# Analog.net
KiCad netlist of a schematic drawn in Altium Designer
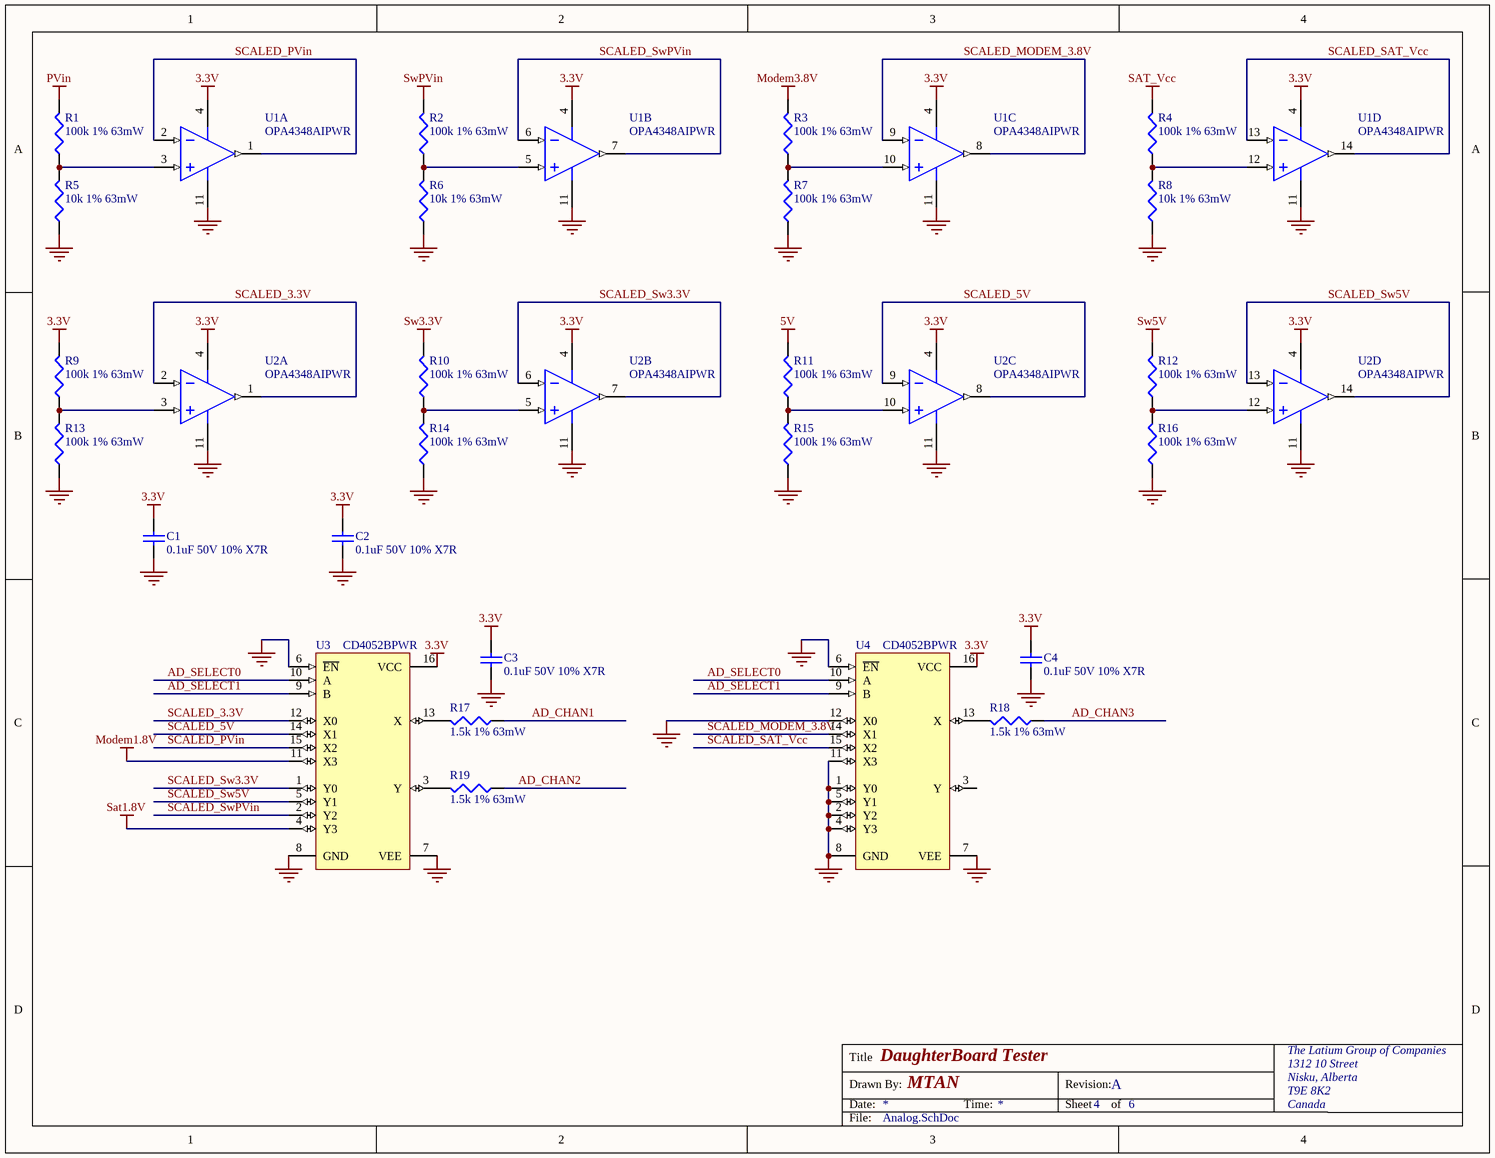
[diagram p0: Analog.SchDoc]

(export (version "E")
  (design (tool "Eeschema 10.0.6"))
  (components
    (comp (ref "C1")
      (value "0.1uF 50V 10% X7R")
      (footprint "CAPC1005L")
      (description "Capacitor")
      (libsource (lib "Miscellaneous Devices") (part "Cap"))
    )
    (comp (ref "C2")
      (value "0.1uF 50V 10% X7R")
      (footprint "CAPC1005L")
      (description "Capacitor")
      (libsource (lib "Miscellaneous Devices") (part "Cap"))
    )
    (comp (ref "C3")
      (value "0.1uF 50V 10% X7R")
      (footprint "CAPC1005L")
      (description "Capacitor")
      (libsource (lib "Miscellaneous Devices") (part "Cap"))
    )
    (comp (ref "C4")
      (value "0.1uF 50V 10% X7R")
      (footprint "CAPC1005L")
      (description "Capacitor")
      (libsource (lib "Miscellaneous Devices") (part "Cap"))
    )
    (comp (ref "R1")
      (value "100k 1% 63mW")
      (footprint "RESC1005L")
      (description "Resistor")
      (libsource (lib "Miscellaneous Devices") (part "Res3"))
    )
    (comp (ref "R2")
      (value "100k 1% 63mW")
      (footprint "RESC1005L")
      (description "Resistor")
      (libsource (lib "Miscellaneous Devices") (part "Res3"))
    )
    (comp (ref "R3")
      (value "100k 1% 63mW")
      (footprint "RESC1005L")
      (description "Resistor")
      (libsource (lib "Miscellaneous Devices") (part "Res3"))
    )
    (comp (ref "R4")
      (value "100k 1% 63mW")
      (footprint "RESC1005L")
      (description "Resistor")
      (libsource (lib "Miscellaneous Devices") (part "Res3"))
    )
    (comp (ref "R5")
      (value "10k 1% 63mW")
      (footprint "RESC1005L")
      (description "Resistor")
      (libsource (lib "Miscellaneous Devices") (part "Res3"))
    )
    (comp (ref "R6")
      (value "10k 1% 63mW")
      (footprint "RESC1005L")
      (description "Resistor")
      (libsource (lib "Miscellaneous Devices") (part "Res3"))
    )
    (comp (ref "R7")
      (value "100k 1% 63mW")
      (footprint "RESC1005L")
      (description "Resistor")
      (libsource (lib "Miscellaneous Devices") (part "Res3"))
    )
    (comp (ref "R8")
      (value "10k 1% 63mW")
      (footprint "RESC1005L")
      (description "Resistor")
      (libsource (lib "Miscellaneous Devices") (part "Res3"))
    )
    (comp (ref "R9")
      (value "100k 1% 63mW")
      (footprint "RESC1005L")
      (description "Resistor")
      (libsource (lib "Miscellaneous Devices") (part "Res3"))
    )
    (comp (ref "R10")
      (value "100k 1% 63mW")
      (footprint "RESC1005L")
      (description "Resistor")
      (libsource (lib "Miscellaneous Devices") (part "Res3"))
    )
    (comp (ref "R11")
      (value "100k 1% 63mW")
      (footprint "RESC1005L")
      (description "Resistor")
      (libsource (lib "Miscellaneous Devices") (part "Res3"))
    )
    (comp (ref "R12")
      (value "100k 1% 63mW")
      (footprint "RESC1005L")
      (description "Resistor")
      (libsource (lib "Miscellaneous Devices") (part "Res3"))
    )
    (comp (ref "R13")
      (value "100k 1% 63mW")
      (footprint "RESC1005L")
      (description "Resistor")
      (libsource (lib "Miscellaneous Devices") (part "Res3"))
    )
    (comp (ref "R14")
      (value "100k 1% 63mW")
      (footprint "RESC1005L")
      (description "Resistor")
      (libsource (lib "Miscellaneous Devices") (part "Res3"))
    )
    (comp (ref "R15")
      (value "100k 1% 63mW")
      (footprint "RESC1005L")
      (description "Resistor")
      (libsource (lib "Miscellaneous Devices") (part "Res3"))
    )
    (comp (ref "R16")
      (value "100k 1% 63mW")
      (footprint "RESC1005L")
      (description "Resistor")
      (libsource (lib "Miscellaneous Devices") (part "Res3"))
    )
    (comp (ref "R17")
      (value "1.5k 1% 63mW")
      (footprint "RESC1005L")
      (description "Resistor")
      (libsource (lib "Miscellaneous Devices") (part "Res3"))
    )
    (comp (ref "R18")
      (value "1.5k 1% 63mW")
      (footprint "RESC1005L")
      (description "Resistor")
      (libsource (lib "Miscellaneous Devices") (part "Res3"))
    )
    (comp (ref "R19")
      (value "1.5k 1% 63mW")
      (footprint "RESC1005L")
      (description "Resistor")
      (libsource (lib "Miscellaneous Devices") (part "Res3"))
    )
    (comp (ref "U1")
      (value "OPA4348AIPWR")
      (footprint "TI-PW14_L")
      (description "IC OPAMP GP 4 CIRCUIT 14TSSOP")
      (fields (field (name "MANUFACTURER") "Texas Instruments"))
      (libsource (lib "TI Amplifiers and Linear Operational Amplifier Precision Amplifier Part One") (part "OPA4348AIPWR"))
    )
    (comp (ref "U2")
      (value "OPA4348AIPWR")
      (footprint "TI-PW14_L")
      (description "IC OPAMP GP 4 CIRCUIT 14TSSOP")
      (fields (field (name "MANUFACTURER") "Texas Instruments"))
      (libsource (lib "TI Amplifiers and Linear Operational Amplifier Precision Amplifier Part One") (part "OPA4348AIPWR"))
    )
    (comp (ref "U3")
      (value "CD4052BPWR")
      (footprint "TSSOP-16_L")
      (description "IC MUX/DEMUX DUAL 4X1 16TSSOP")
      (fields (field (name "MANUFACTURER") "Texas Instruments"))
      (libsource (lib "FSC Logic Multiplexer") (part "CD4052BCM"))
    )
    (comp (ref "U4")
      (value "CD4052BPWR")
      (footprint "TSSOP-16_L")
      (description "IC MUX/DEMUX DUAL 4X1 16TSSOP")
      (fields (field (name "MANUFACTURER") "Texas Instruments"))
      (libsource (lib "FSC Logic Multiplexer") (part "CD4052BCM"))
    )
  )
  (nets
    (net (code "1") (name "/AD_CHAN1") (class "Default")
      (node (ref "R17") (pin "1") (pinfunction "1_1") (pintype "passive"))
    )
    (net (code "2") (name "/AD_CHAN2") (class "Default")
      (node (ref "R19") (pin "1") (pinfunction "1_1") (pintype "passive"))
    )
    (net (code "3") (name "/AD_CHAN3") (class "Default")
      (node (ref "R18") (pin "1") (pinfunction "1_1") (pintype "passive"))
    )
    (net (code "4") (name "/AD_SELECT0") (class "Default")
      (node (ref "U3") (pin "10") (pinfunction "A_10") (pintype "input"))
      (node (ref "U4") (pin "10") (pinfunction "A_10") (pintype "input"))
    )
    (net (code "5") (name "/AD_SELECT1") (class "Default")
      (node (ref "U3") (pin "9") (pinfunction "B_9") (pintype "input"))
      (node (ref "U4") (pin "9") (pinfunction "B_9") (pintype "input"))
    )
    (net (code "6") (name "/SCALED_3.3V") (class "Default")
      (node (ref "U2") (pin "1") (pinfunction "OUT_A_1") (pintype "output"))
      (node (ref "U2") (pin "2") (pinfunction "IN_A-_2") (pintype "input"))
      (node (ref "U3") (pin "12") (pinfunction "X0_12") (pintype "bidirectional"))
    )
    (net (code "7") (name "/SCALED_5V") (class "Default")
      (node (ref "U2") (pin "8") (pinfunction "OUT_C_8") (pintype "output"))
      (node (ref "U2") (pin "9") (pinfunction "IN_C-_9") (pintype "input"))
      (node (ref "U3") (pin "14") (pinfunction "X1_14") (pintype "bidirectional"))
    )
    (net (code "8") (name "/SCALED_MODEM_3.8V") (class "Default")
      (node (ref "U1") (pin "8") (pinfunction "OUT_C_8") (pintype "output"))
      (node (ref "U1") (pin "9") (pinfunction "IN_C-_9") (pintype "input"))
      (node (ref "U4") (pin "14") (pinfunction "X1_14") (pintype "bidirectional"))
    )
    (net (code "9") (name "/SCALED_PVin") (class "Default")
      (node (ref "U1") (pin "1") (pinfunction "OUT_A_1") (pintype "output"))
      (node (ref "U1") (pin "2") (pinfunction "IN_A-_2") (pintype "input"))
      (node (ref "U3") (pin "15") (pinfunction "X2_15") (pintype "bidirectional"))
    )
    (net (code "10") (name "/SCALED_SAT_Vcc") (class "Default")
      (node (ref "U1") (pin "13") (pinfunction "IN_D-_13") (pintype "input"))
      (node (ref "U1") (pin "14") (pinfunction "OUT_D_14") (pintype "output"))
      (node (ref "U4") (pin "15") (pinfunction "X2_15") (pintype "bidirectional"))
    )
    (net (code "11") (name "/SCALED_Sw3.3V") (class "Default")
      (node (ref "U2") (pin "6") (pinfunction "IN_B-_6") (pintype "input"))
      (node (ref "U2") (pin "7") (pinfunction "OUT_B_7") (pintype "output"))
      (node (ref "U3") (pin "1") (pinfunction "Y0_1") (pintype "bidirectional"))
    )
    (net (code "12") (name "/SCALED_Sw5V") (class "Default")
      (node (ref "U2") (pin "13") (pinfunction "IN_D-_13") (pintype "input"))
      (node (ref "U2") (pin "14") (pinfunction "OUT_D_14") (pintype "output"))
      (node (ref "U3") (pin "5") (pinfunction "Y1_5") (pintype "bidirectional"))
    )
    (net (code "13") (name "/SCALED_SwPVin") (class "Default")
      (node (ref "U1") (pin "6") (pinfunction "IN_B-_6") (pintype "input"))
      (node (ref "U1") (pin "7") (pinfunction "OUT_B_7") (pintype "output"))
      (node (ref "U3") (pin "2") (pinfunction "Y2_2") (pintype "bidirectional"))
    )
    (net (code "14") (name "3.3V") (class "Default")
      (node (ref "C1") (pin "1") (pinfunction "1_1") (pintype "passive"))
      (node (ref "C2") (pin "1") (pinfunction "1_1") (pintype "passive"))
      (node (ref "C3") (pin "1") (pinfunction "1_1") (pintype "passive"))
      (node (ref "C4") (pin "1") (pinfunction "1_1") (pintype "passive"))
      (node (ref "R9") (pin "2") (pinfunction "2_2") (pintype "passive"))
      (node (ref "U1") (pin "4") (pinfunction "V+_4") (pintype "power_in"))
      (node (ref "U2") (pin "4") (pinfunction "V+_4") (pintype "power_in"))
      (node (ref "U3") (pin "16") (pinfunction "VCC_16") (pintype "power_in"))
      (node (ref "U4") (pin "16") (pinfunction "VCC_16") (pintype "power_in"))
    )
    (net (code "15") (name "5V") (class "Default")
      (node (ref "R11") (pin "2") (pinfunction "2_2") (pintype "passive"))
    )
    (net (code "16") (name "GND") (class "Default")
      (node (ref "C1") (pin "2") (pinfunction "2_2") (pintype "passive"))
      (node (ref "C2") (pin "2") (pinfunction "2_2") (pintype "passive"))
      (node (ref "C3") (pin "2") (pinfunction "2_2") (pintype "passive"))
      (node (ref "C4") (pin "2") (pinfunction "2_2") (pintype "passive"))
      (node (ref "R13") (pin "1") (pinfunction "1_1") (pintype "passive"))
      (node (ref "R14") (pin "1") (pinfunction "1_1") (pintype "passive"))
      (node (ref "R15") (pin "1") (pinfunction "1_1") (pintype "passive"))
      (node (ref "R16") (pin "1") (pinfunction "1_1") (pintype "passive"))
      (node (ref "R5") (pin "1") (pinfunction "1_1") (pintype "passive"))
      (node (ref "R6") (pin "1") (pinfunction "1_1") (pintype "passive"))
      (node (ref "R7") (pin "1") (pinfunction "1_1") (pintype "passive"))
      (node (ref "R8") (pin "1") (pinfunction "1_1") (pintype "passive"))
      (node (ref "U1") (pin "11") (pinfunction "V-_11") (pintype "power_in"))
      (node (ref "U2") (pin "11") (pinfunction "V-_11") (pintype "power_in"))
      (node (ref "U3") (pin "6") (pinfunction "~{EN}_6") (pintype "input"))
      (node (ref "U3") (pin "7") (pinfunction "VEE_7") (pintype "power_in"))
      (node (ref "U3") (pin "8") (pinfunction "GND_8") (pintype "power_in"))
      (node (ref "U4") (pin "1") (pinfunction "Y0_1") (pintype "bidirectional"))
      (node (ref "U4") (pin "11") (pinfunction "X3_11") (pintype "bidirectional"))
      (node (ref "U4") (pin "12") (pinfunction "X0_12") (pintype "bidirectional"))
      (node (ref "U4") (pin "2") (pinfunction "Y2_2") (pintype "bidirectional"))
      (node (ref "U4") (pin "4") (pinfunction "Y3_4") (pintype "bidirectional"))
      (node (ref "U4") (pin "5") (pinfunction "Y1_5") (pintype "bidirectional"))
      (node (ref "U4") (pin "6") (pinfunction "~{EN}_6") (pintype "input"))
      (node (ref "U4") (pin "7") (pinfunction "VEE_7") (pintype "power_in"))
      (node (ref "U4") (pin "8") (pinfunction "GND_8") (pintype "power_in"))
    )
    (net (code "17") (name "Modem1.8V") (class "Default")
      (node (ref "U3") (pin "11") (pinfunction "X3_11") (pintype "bidirectional"))
    )
    (net (code "18") (name "Modem3.8V") (class "Default")
      (node (ref "R3") (pin "2") (pinfunction "2_2") (pintype "passive"))
    )
    (net (code "19") (name "Net-(U1A-IN_A+)") (class "Default")
      (node (ref "R1") (pin "1") (pinfunction "1_1") (pintype "passive"))
      (node (ref "R5") (pin "2") (pinfunction "2_2") (pintype "passive"))
      (node (ref "U1") (pin "3") (pinfunction "IN_A+_3") (pintype "input"))
    )
    (net (code "20") (name "Net-(U1B-IN_B+)") (class "Default")
      (node (ref "R2") (pin "1") (pinfunction "1_1") (pintype "passive"))
      (node (ref "R6") (pin "2") (pinfunction "2_2") (pintype "passive"))
      (node (ref "U1") (pin "5") (pinfunction "IN_B+_5") (pintype "input"))
    )
    (net (code "21") (name "Net-(U1C-IN_C+)") (class "Default")
      (node (ref "R3") (pin "1") (pinfunction "1_1") (pintype "passive"))
      (node (ref "R7") (pin "2") (pinfunction "2_2") (pintype "passive"))
      (node (ref "U1") (pin "10") (pinfunction "IN_C+_10") (pintype "input"))
    )
    (net (code "22") (name "Net-(U1D-IN_D+)") (class "Default")
      (node (ref "R4") (pin "1") (pinfunction "1_1") (pintype "passive"))
      (node (ref "R8") (pin "2") (pinfunction "2_2") (pintype "passive"))
      (node (ref "U1") (pin "12") (pinfunction "IN_D+_12") (pintype "input"))
    )
    (net (code "23") (name "Net-(U2A-IN_A+)") (class "Default")
      (node (ref "R13") (pin "2") (pinfunction "2_2") (pintype "passive"))
      (node (ref "R9") (pin "1") (pinfunction "1_1") (pintype "passive"))
      (node (ref "U2") (pin "3") (pinfunction "IN_A+_3") (pintype "input"))
    )
    (net (code "24") (name "Net-(U2B-IN_B+)") (class "Default")
      (node (ref "R10") (pin "1") (pinfunction "1_1") (pintype "passive"))
      (node (ref "R14") (pin "2") (pinfunction "2_2") (pintype "passive"))
      (node (ref "U2") (pin "5") (pinfunction "IN_B+_5") (pintype "input"))
    )
    (net (code "25") (name "Net-(U2C-IN_C+)") (class "Default")
      (node (ref "R11") (pin "1") (pinfunction "1_1") (pintype "passive"))
      (node (ref "R15") (pin "2") (pinfunction "2_2") (pintype "passive"))
      (node (ref "U2") (pin "10") (pinfunction "IN_C+_10") (pintype "input"))
    )
    (net (code "26") (name "Net-(U2D-IN_D+)") (class "Default")
      (node (ref "R12") (pin "1") (pinfunction "1_1") (pintype "passive"))
      (node (ref "R16") (pin "2") (pinfunction "2_2") (pintype "passive"))
      (node (ref "U2") (pin "12") (pinfunction "IN_D+_12") (pintype "input"))
    )
    (net (code "27") (name "Net-(U3-X)") (class "Default")
      (node (ref "R17") (pin "2") (pinfunction "2_2") (pintype "passive"))
      (node (ref "U3") (pin "13") (pinfunction "X_13") (pintype "bidirectional"))
    )
    (net (code "28") (name "Net-(U3-Y)") (class "Default")
      (node (ref "R19") (pin "2") (pinfunction "2_2") (pintype "passive"))
      (node (ref "U3") (pin "3") (pinfunction "Y_3") (pintype "bidirectional"))
    )
    (net (code "29") (name "Net-(U4-X)") (class "Default")
      (node (ref "R18") (pin "2") (pinfunction "2_2") (pintype "passive"))
      (node (ref "U4") (pin "13") (pinfunction "X_13") (pintype "bidirectional"))
    )
    (net (code "30") (name "PVin") (class "Default")
      (node (ref "R1") (pin "2") (pinfunction "2_2") (pintype "passive"))
    )
    (net (code "31") (name "SAT_Vcc") (class "Default")
      (node (ref "R4") (pin "2") (pinfunction "2_2") (pintype "passive"))
    )
    (net (code "32") (name "Sat1.8V") (class "Default")
      (node (ref "U3") (pin "4") (pinfunction "Y3_4") (pintype "bidirectional"))
    )
    (net (code "33") (name "Sw3.3V") (class "Default")
      (node (ref "R10") (pin "2") (pinfunction "2_2") (pintype "passive"))
    )
    (net (code "34") (name "Sw5V") (class "Default")
      (node (ref "R12") (pin "2") (pinfunction "2_2") (pintype "passive"))
    )
    (net (code "35") (name "SwPVin") (class "Default")
      (node (ref "R2") (pin "2") (pinfunction "2_2") (pintype "passive"))
    )
    (net (code "36") (name "unconnected-(U4-Y-Pad3)") (class "Default")
      (node (ref "U4") (pin "3") (pinfunction "Y_3") (pintype "bidirectional"))
    )
  )
)
